# electrosteel2020_10_arrange6_newstringco.net
KiCad netlist of a schematic drawn in EAGLE
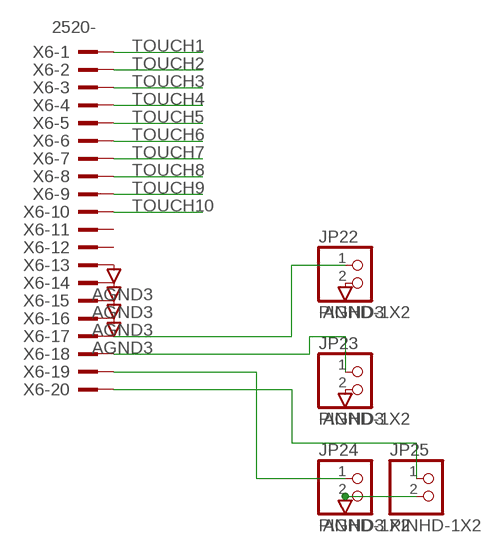
[diagram p0: schematic, sheet 1]

(export (version "E")
  (design (tool "Eeschema 10.0.6"))
  (components
    (comp (ref "JP22")
      (value "PINHD-1X2")
      (footprint "eagle-import:1X02")
      (fields (field (name "PARTNO") "*DNP"))
      (libsource (lib "eagle-import") (part "PINHD-1X2"))
    )
    (comp (ref "JP23")
      (value "PINHD-1X2")
      (footprint "eagle-import:1X02")
      (fields (field (name "PARTNO") "*DNP"))
      (libsource (lib "eagle-import") (part "PINHD-1X2"))
    )
    (comp (ref "JP24")
      (value "PINHD-1X2")
      (footprint "eagle-import:1X02")
      (fields (field (name "PARTNO") "*DNP"))
      (libsource (lib "eagle-import") (part "PINHD-1X2"))
    )
    (comp (ref "JP25")
      (value "PINHD-1X2")
      (footprint "eagle-import:1X02")
      (fields (field (name "PARTNO") "*DNP"))
      (libsource (lib "eagle-import") (part "PINHD-1X2"))
    )
    (comp (ref "X6")
      (value "2520-")
      (footprint "eagle-import:PAK100_2500-20")
      (fields (field (name "PARTNO") "N2520-6003-UG"))
      (libsource (lib "eagle-import") (part "2520-"))
    )
  )
  (nets
    (net (code "1") (name "/TOUCH1") (class "Default")
      (node (ref "X6") (pin "1") (pinfunction "KL_1") (pintype "passive"))
    )
    (net (code "2") (name "/TOUCH2") (class "Default")
      (node (ref "X6") (pin "2") (pinfunction "KL_2") (pintype "passive"))
    )
    (net (code "3") (name "/TOUCH3") (class "Default")
      (node (ref "X6") (pin "3") (pinfunction "KL_3") (pintype "passive"))
    )
    (net (code "4") (name "/TOUCH4") (class "Default")
      (node (ref "X6") (pin "4") (pinfunction "KL_4") (pintype "passive"))
    )
    (net (code "5") (name "/TOUCH5") (class "Default")
      (node (ref "X6") (pin "5") (pinfunction "KL_5") (pintype "passive"))
    )
    (net (code "6") (name "/TOUCH6") (class "Default")
      (node (ref "X6") (pin "6") (pinfunction "KL_6") (pintype "passive"))
    )
    (net (code "7") (name "/TOUCH7") (class "Default")
      (node (ref "X6") (pin "7") (pinfunction "KL_7") (pintype "passive"))
    )
    (net (code "8") (name "/TOUCH8") (class "Default")
      (node (ref "X6") (pin "8") (pinfunction "KL_8") (pintype "passive"))
    )
    (net (code "9") (name "/TOUCH9") (class "Default")
      (node (ref "X6") (pin "9") (pinfunction "KL_9") (pintype "passive"))
    )
    (net (code "10") (name "/TOUCH10") (class "Default")
      (node (ref "X6") (pin "10") (pinfunction "KL_10") (pintype "passive"))
    )
    (net (code "11") (name "AGND3") (class "Default")
      (node (ref "JP22") (pin "2") (pinfunction "2_2") (pintype "passive"))
      (node (ref "JP23") (pin "2") (pinfunction "2_2") (pintype "passive"))
      (node (ref "JP24") (pin "2") (pinfunction "2_2") (pintype "passive"))
      (node (ref "JP25") (pin "2") (pinfunction "2_2") (pintype "passive"))
      (node (ref "X6") (pin "13") (pinfunction "KL_13") (pintype "passive"))
      (node (ref "X6") (pin "14") (pinfunction "KL_14") (pintype "passive"))
      (node (ref "X6") (pin "15") (pinfunction "KL_15") (pintype "passive"))
      (node (ref "X6") (pin "16") (pinfunction "KL_16") (pintype "passive"))
    )
    (net (code "12") (name "Net-(X6I-KL)") (class "Default")
      (node (ref "JP22") (pin "1") (pinfunction "1_1") (pintype "passive"))
      (node (ref "X6") (pin "17") (pinfunction "KL_17") (pintype "passive"))
    )
    (net (code "13") (name "Net-(X6J-KL)") (class "Default")
      (node (ref "JP23") (pin "1") (pinfunction "1_1") (pintype "passive"))
      (node (ref "X6") (pin "18") (pinfunction "KL_18") (pintype "passive"))
    )
    (net (code "14") (name "Net-(X6K-KL)") (class "Default")
      (node (ref "JP24") (pin "1") (pinfunction "1_1") (pintype "passive"))
      (node (ref "X6") (pin "19") (pinfunction "KL_19") (pintype "passive"))
    )
    (net (code "15") (name "Net-(X6M-KL)") (class "Default")
      (node (ref "JP25") (pin "1") (pinfunction "1_1") (pintype "passive"))
      (node (ref "X6") (pin "20") (pinfunction "KL_20") (pintype "passive"))
    )
    (net (code "16") (name "unconnected-(X6C-KL-Pad11)") (class "Default")
      (node (ref "X6") (pin "11") (pinfunction "KL_11") (pintype "passive"))
    )
    (net (code "17") (name "unconnected-(X6D-KL-Pad12)") (class "Default")
      (node (ref "X6") (pin "12") (pinfunction "KL_12") (pintype "passive"))
    )
  )
)
